# QDRII_mem.net
KiCad netlist of a schematic drawn in Altium Designer
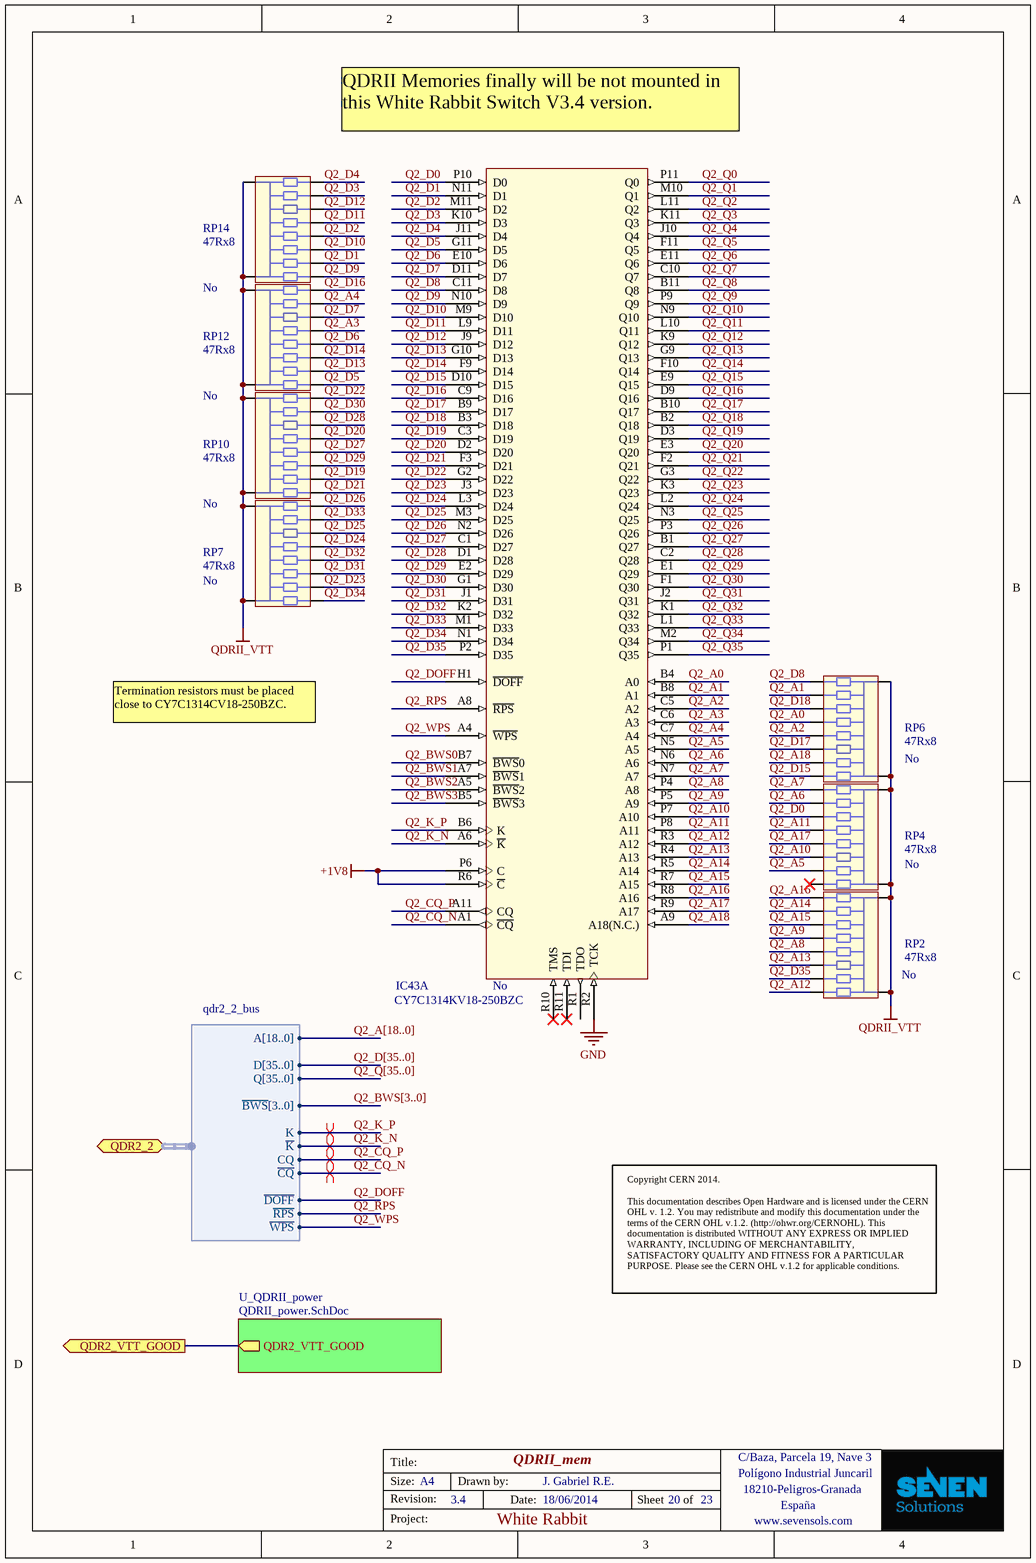
[diagram p0: QDRII_mem.SchDoc]

(export (version "E")
  (design (tool "Eeschema 10.0.6"))
  (components
    (comp (ref "IC43")
      (value "CY7C1314KV18-250BZC")
      (footprint "BGA165C100P11X15_1300X1500X140")
      (description "18-Mbit (512Kx36) QDRII SRAM 2-Word Burst Architecture")
      (fields (field (name "MOUNTED") "No"))
      (libsource (lib "wr_switch") (part "CY7C1314CV18"))
    )
    (comp (ref "RP2")
      (value "47Rx8")
      (footprint "EXBE")
      (description "47R, 62.5mW Chip Resistor Bussed Network")
      (fields
        (field (name "TOLERANCE") "±5%")
        (field (name "MOUNTED") "No")
        (field (name "Comment") "47R x 8")
      )
      (libsource (lib "") (part "EXB-E10C470J_1"))
    )
    (comp (ref "RP4")
      (value "47Rx8")
      (footprint "EXBE")
      (description "47R, 62.5mW Chip Resistor Bussed Network")
      (fields
        (field (name "TOLERANCE") "±5%")
        (field (name "MOUNTED") "No")
        (field (name "Comment") "47R x 8")
      )
      (libsource (lib "") (part "EXB-E10C470J_4"))
    )
    (comp (ref "RP6")
      (value "47Rx8")
      (footprint "EXBE")
      (description "47R, 62.5mW Chip Resistor Bussed Network")
      (fields
        (field (name "TOLERANCE") "±5%")
        (field (name "MOUNTED") "No")
        (field (name "Comment") "47R x 8")
      )
      (libsource (lib "") (part "EXB-E10C470J_3"))
    )
    (comp (ref "RP7")
      (value "47Rx8")
      (footprint "EXBE")
      (description "47R, 62.5mW Chip Resistor Bussed Network")
      (fields
        (field (name "TOLERANCE") "±5%")
        (field (name "MOUNTED") "No")
        (field (name "Comment") "47R x 8")
      )
      (libsource (lib "") (part "EXB-E10C470J_5"))
    )
    (comp (ref "RP10")
      (value "47Rx8")
      (footprint "EXBE")
      (description "47R, 62.5mW Chip Resistor Bussed Network")
      (fields
        (field (name "TOLERANCE") "±5%")
        (field (name "MOUNTED") "No")
        (field (name "Comment") "47R x 8")
      )
      (libsource (lib "") (part "EXB-E10C470J_2"))
    )
    (comp (ref "RP12")
      (value "47Rx8")
      (footprint "EXBE")
      (description "47R, 62.5mW Chip Resistor Bussed Network")
      (fields
        (field (name "TOLERANCE") "±5%")
        (field (name "MOUNTED") "No")
        (field (name "Comment") "47R x 8")
      )
      (libsource (lib "wr_switch") (part "EXB-E10C470J"))
    )
    (comp (ref "RP14")
      (value "47Rx8")
      (footprint "EXBE")
      (description "47R, 62.5mW Chip Resistor Bussed Network")
      (fields
        (field (name "TOLERANCE") "±5%")
        (field (name "MOUNTED") "No")
        (field (name "Comment") "47R x 8")
      )
      (libsource (lib "wr_switch") (part "EXB-E10C470J"))
    )
  )
  (nets
    (net (code "2") (name "+1V8") (class "Default")
      (node (ref "IC43") (pin "P6") (pinfunction "C_P6") (pintype "input"))
      (node (ref "IC43") (pin "R6") (pinfunction "~{C}_R6") (pintype "input"))
    )
    (net (code "3") (name "/Q2_A0") (class "Default")
      (node (ref "IC43") (pin "B4") (pinfunction "A0_B4") (pintype "input"))
      (node (ref "RP6") (pin "8") (pinfunction "8_8") (pintype "passive"))
    )
    (net (code "4") (name "/Q2_A1") (class "Default")
      (node (ref "IC43") (pin "B8") (pinfunction "A1_B8") (pintype "input"))
      (node (ref "RP6") (pin "10") (pinfunction "10_10") (pintype "passive"))
    )
    (net (code "5") (name "/Q2_A2") (class "Default")
      (node (ref "IC43") (pin "C5") (pinfunction "A2_C5") (pintype "input"))
      (node (ref "RP6") (pin "9") (pinfunction "9_9") (pintype "passive"))
    )
    (net (code "6") (name "/Q2_A3") (class "Default")
      (node (ref "IC43") (pin "C6") (pinfunction "A3_C6") (pintype "input"))
      (node (ref "RP12") (pin "7") (pinfunction "7_7") (pintype "passive"))
    )
    (net (code "7") (name "/Q2_A4") (class "Default")
      (node (ref "IC43") (pin "C7") (pinfunction "A4_C7") (pintype "input"))
      (node (ref "RP12") (pin "9") (pinfunction "9_9") (pintype "passive"))
    )
    (net (code "8") (name "/Q2_A5") (class "Default")
      (node (ref "IC43") (pin "N5") (pinfunction "A5_N5") (pintype "input"))
      (node (ref "RP4") (pin "8") (pinfunction "8_8") (pintype "passive"))
    )
    (net (code "9") (name "/Q2_A6") (class "Default")
      (node (ref "IC43") (pin "N6") (pinfunction "A6_N6") (pintype "input"))
      (node (ref "RP4") (pin "9") (pinfunction "9_9") (pintype "passive"))
    )
    (net (code "10") (name "/Q2_A7") (class "Default")
      (node (ref "IC43") (pin "N7") (pinfunction "A7_N7") (pintype "input"))
      (node (ref "RP4") (pin "10") (pinfunction "10_10") (pintype "passive"))
    )
    (net (code "11") (name "/Q2_A8") (class "Default")
      (node (ref "IC43") (pin "P4") (pinfunction "A8_P4") (pintype "input"))
      (node (ref "RP2") (pin "5") (pinfunction "5_5") (pintype "passive"))
    )
    (net (code "12") (name "/Q2_A9") (class "Default")
      (node (ref "IC43") (pin "P5") (pinfunction "A9_P5") (pintype "input"))
      (node (ref "RP2") (pin "8") (pinfunction "8_8") (pintype "passive"))
    )
    (net (code "13") (name "/Q2_A10") (class "Default")
      (node (ref "IC43") (pin "P7") (pinfunction "A10_P7") (pintype "input"))
      (node (ref "RP4") (pin "2") (pinfunction "2_2") (pintype "passive"))
    )
    (net (code "14") (name "/Q2_A11") (class "Default")
      (node (ref "IC43") (pin "P8") (pinfunction "A11_P8") (pintype "input"))
      (node (ref "RP4") (pin "3") (pinfunction "3_3") (pintype "passive"))
    )
    (net (code "15") (name "/Q2_A12") (class "Default")
      (node (ref "IC43") (pin "R3") (pinfunction "A12_R3") (pintype "input"))
      (node (ref "RP2") (pin "2") (pinfunction "2_2") (pintype "passive"))
    )
    (net (code "16") (name "/Q2_A13") (class "Default")
      (node (ref "IC43") (pin "R4") (pinfunction "A13_R4") (pintype "input"))
      (node (ref "RP2") (pin "4") (pinfunction "4_4") (pintype "passive"))
    )
    (net (code "17") (name "/Q2_A14") (class "Default")
      (node (ref "IC43") (pin "R5") (pinfunction "A14_R5") (pintype "input"))
      (node (ref "RP2") (pin "7") (pinfunction "7_7") (pintype "passive"))
    )
    (net (code "18") (name "/Q2_A15") (class "Default")
      (node (ref "IC43") (pin "R7") (pinfunction "A15_R7") (pintype "input"))
      (node (ref "RP2") (pin "9") (pinfunction "9_9") (pintype "passive"))
    )
    (net (code "19") (name "/Q2_A16") (class "Default")
      (node (ref "IC43") (pin "R8") (pinfunction "A16_R8") (pintype "input"))
      (node (ref "RP2") (pin "10") (pinfunction "10_10") (pintype "passive"))
    )
    (net (code "20") (name "/Q2_A17") (class "Default")
      (node (ref "IC43") (pin "R9") (pinfunction "A17_R9") (pintype "input"))
      (node (ref "RP4") (pin "4") (pinfunction "4_4") (pintype "passive"))
    )
    (net (code "21") (name "/Q2_A18") (class "Default")
      (node (ref "IC43") (pin "A9") (pinfunction "A18(N.C.)_A9") (pintype "input"))
      (node (ref "RP6") (pin "3") (pinfunction "3_3") (pintype "passive"))
    )
    (net (code "23") (name "/Q2_BWS0") (class "Default")
      (node (ref "IC43") (pin "B7") (pinfunction "~{BWS}0_B7") (pintype "input"))
    )
    (net (code "24") (name "/Q2_BWS1") (class "Default")
      (node (ref "IC43") (pin "A7") (pinfunction "~{BWS}1_A7") (pintype "input"))
    )
    (net (code "25") (name "/Q2_BWS2") (class "Default")
      (node (ref "IC43") (pin "A5") (pinfunction "~{BWS}2_A5") (pintype "input"))
    )
    (net (code "26") (name "/Q2_BWS3") (class "Default")
      (node (ref "IC43") (pin "B5") (pinfunction "~{BWS}3_B5") (pintype "input"))
    )
    (net (code "27") (name "/Q2_CQ_N") (class "Default")
      (node (ref "IC43") (pin "A1") (pinfunction "~{CQ}_A1") (pintype "output"))
    )
    (net (code "28") (name "/Q2_CQ_P") (class "Default")
      (node (ref "IC43") (pin "A11") (pinfunction "CQ_A11") (pintype "output"))
    )
    (net (code "29") (name "/Q2_D0") (class "Default")
      (node (ref "IC43") (pin "P10") (pinfunction "D0_P10") (pintype "input"))
      (node (ref "RP4") (pin "5") (pinfunction "5_5") (pintype "passive"))
    )
    (net (code "30") (name "/Q2_D1") (class "Default")
      (node (ref "IC43") (pin "N11") (pinfunction "D1_N11") (pintype "input"))
      (node (ref "RP14") (pin "3") (pinfunction "3_3") (pintype "passive"))
    )
    (net (code "31") (name "/Q2_D2") (class "Default")
      (node (ref "IC43") (pin "M11") (pinfunction "D2_M11") (pintype "input"))
      (node (ref "RP14") (pin "5") (pinfunction "5_5") (pintype "passive"))
    )
    (net (code "32") (name "/Q2_D3") (class "Default")
      (node (ref "IC43") (pin "K10") (pinfunction "D3_K10") (pintype "input"))
      (node (ref "RP14") (pin "9") (pinfunction "9_9") (pintype "passive"))
    )
    (net (code "33") (name "/Q2_D4") (class "Default")
      (node (ref "IC43") (pin "J11") (pinfunction "D4_J11") (pintype "input"))
      (node (ref "RP14") (pin "10") (pinfunction "10_10") (pintype "passive"))
    )
    (net (code "34") (name "/Q2_D5") (class "Default")
      (node (ref "IC43") (pin "G11") (pinfunction "D5_G11") (pintype "input"))
      (node (ref "RP12") (pin "2") (pinfunction "2_2") (pintype "passive"))
    )
    (net (code "35") (name "/Q2_D6") (class "Default")
      (node (ref "IC43") (pin "E10") (pinfunction "D6_E10") (pintype "input"))
      (node (ref "RP12") (pin "5") (pinfunction "5_5") (pintype "passive"))
    )
    (net (code "36") (name "/Q2_D7") (class "Default")
      (node (ref "IC43") (pin "D11") (pinfunction "D7_D11") (pintype "input"))
      (node (ref "RP12") (pin "8") (pinfunction "8_8") (pintype "passive"))
    )
    (net (code "37") (name "/Q2_D8") (class "Default")
      (node (ref "IC43") (pin "C11") (pinfunction "D8_C11") (pintype "input"))
      (node (ref "RP6") (pin "5") (pinfunction "5_5") (pintype "passive"))
    )
    (net (code "38") (name "/Q2_D9") (class "Default")
      (node (ref "IC43") (pin "N10") (pinfunction "D9_N10") (pintype "input"))
      (node (ref "RP14") (pin "2") (pinfunction "2_2") (pintype "passive"))
    )
    (net (code "39") (name "/Q2_D10") (class "Default")
      (node (ref "IC43") (pin "M9") (pinfunction "D10_M9") (pintype "input"))
      (node (ref "RP14") (pin "4") (pinfunction "4_4") (pintype "passive"))
    )
    (net (code "40") (name "/Q2_D11") (class "Default")
      (node (ref "IC43") (pin "L9") (pinfunction "D11_L9") (pintype "input"))
      (node (ref "RP14") (pin "7") (pinfunction "7_7") (pintype "passive"))
    )
    (net (code "41") (name "/Q2_D12") (class "Default")
      (node (ref "IC43") (pin "J9") (pinfunction "D12_J9") (pintype "input"))
      (node (ref "RP14") (pin "8") (pinfunction "8_8") (pintype "passive"))
    )
    (net (code "42") (name "/Q2_D13") (class "Default")
      (node (ref "IC43") (pin "G10") (pinfunction "D13_G10") (pintype "input"))
      (node (ref "RP12") (pin "3") (pinfunction "3_3") (pintype "passive"))
    )
    (net (code "43") (name "/Q2_D14") (class "Default")
      (node (ref "IC43") (pin "F9") (pinfunction "D14_F9") (pintype "input"))
      (node (ref "RP12") (pin "4") (pinfunction "4_4") (pintype "passive"))
    )
    (net (code "44") (name "/Q2_D15") (class "Default")
      (node (ref "IC43") (pin "D10") (pinfunction "D15_D10") (pintype "input"))
      (node (ref "RP6") (pin "4") (pinfunction "4_4") (pintype "passive"))
    )
    (net (code "45") (name "/Q2_D16") (class "Default")
      (node (ref "IC43") (pin "C9") (pinfunction "D16_C9") (pintype "input"))
      (node (ref "RP12") (pin "10") (pinfunction "10_10") (pintype "passive"))
    )
    (net (code "46") (name "/Q2_D17") (class "Default")
      (node (ref "IC43") (pin "B9") (pinfunction "D17_B9") (pintype "input"))
      (node (ref "RP6") (pin "2") (pinfunction "2_2") (pintype "passive"))
    )
    (net (code "47") (name "/Q2_D18") (class "Default")
      (node (ref "IC43") (pin "B3") (pinfunction "D18_B3") (pintype "input"))
      (node (ref "RP6") (pin "7") (pinfunction "7_7") (pintype "passive"))
    )
    (net (code "48") (name "/Q2_D19") (class "Default")
      (node (ref "IC43") (pin "C3") (pinfunction "D19_C3") (pintype "input"))
      (node (ref "RP10") (pin "7") (pinfunction "7_7") (pintype "passive"))
    )
    (net (code "49") (name "/Q2_D20") (class "Default")
      (node (ref "IC43") (pin "D2") (pinfunction "D20_D2") (pintype "input"))
      (node (ref "RP10") (pin "9") (pinfunction "9_9") (pintype "passive"))
    )
    (net (code "50") (name "/Q2_D21") (class "Default")
      (node (ref "IC43") (pin "F3") (pinfunction "D21_F3") (pintype "input"))
      (node (ref "RP10") (pin "3") (pinfunction "3_3") (pintype "passive"))
    )
    (net (code "51") (name "/Q2_D22") (class "Default")
      (node (ref "IC43") (pin "G2") (pinfunction "D22_G2") (pintype "input"))
      (node (ref "RP10") (pin "5") (pinfunction "5_5") (pintype "passive"))
    )
    (net (code "52") (name "/Q2_D23") (class "Default")
      (node (ref "IC43") (pin "J3") (pinfunction "D23_J3") (pintype "input"))
      (node (ref "RP7") (pin "7") (pinfunction "7_7") (pintype "passive"))
    )
    (net (code "53") (name "/Q2_D24") (class "Default")
      (node (ref "IC43") (pin "L3") (pinfunction "D24_L3") (pintype "input"))
      (node (ref "RP7") (pin "10") (pinfunction "10_10") (pintype "passive"))
    )
    (net (code "54") (name "/Q2_D25") (class "Default")
      (node (ref "IC43") (pin "M3") (pinfunction "D25_M3") (pintype "input"))
      (node (ref "RP7") (pin "2") (pinfunction "2_2") (pintype "passive"))
    )
    (net (code "55") (name "/Q2_D26") (class "Default")
      (node (ref "IC43") (pin "N2") (pinfunction "D26_N2") (pintype "input"))
      (node (ref "RP7") (pin "4") (pinfunction "4_4") (pintype "passive"))
    )
    (net (code "56") (name "/Q2_D27") (class "Default")
      (node (ref "IC43") (pin "C1") (pinfunction "D27_C1") (pintype "input"))
      (node (ref "RP10") (pin "8") (pinfunction "8_8") (pintype "passive"))
    )
    (net (code "57") (name "/Q2_D28") (class "Default")
      (node (ref "IC43") (pin "D1") (pinfunction "D28_D1") (pintype "input"))
      (node (ref "RP10") (pin "10") (pinfunction "10_10") (pintype "passive"))
    )
    (net (code "58") (name "/Q2_D29") (class "Default")
      (node (ref "IC43") (pin "E2") (pinfunction "D29_E2") (pintype "input"))
      (node (ref "RP10") (pin "2") (pinfunction "2_2") (pintype "passive"))
    )
    (net (code "59") (name "/Q2_D30") (class "Default")
      (node (ref "IC43") (pin "G1") (pinfunction "D30_G1") (pintype "input"))
      (node (ref "RP10") (pin "4") (pinfunction "4_4") (pintype "passive"))
    )
    (net (code "60") (name "/Q2_D31") (class "Default")
      (node (ref "IC43") (pin "J1") (pinfunction "D31_J1") (pintype "input"))
      (node (ref "RP7") (pin "8") (pinfunction "8_8") (pintype "passive"))
    )
    (net (code "61") (name "/Q2_D32") (class "Default")
      (node (ref "IC43") (pin "K2") (pinfunction "D32_K2") (pintype "input"))
      (node (ref "RP7") (pin "9") (pinfunction "9_9") (pintype "passive"))
    )
    (net (code "62") (name "/Q2_D33") (class "Default")
      (node (ref "IC43") (pin "M1") (pinfunction "D33_M1") (pintype "input"))
      (node (ref "RP7") (pin "3") (pinfunction "3_3") (pintype "passive"))
    )
    (net (code "63") (name "/Q2_D34") (class "Default")
      (node (ref "IC43") (pin "N1") (pinfunction "D34_N1") (pintype "input"))
      (node (ref "RP7") (pin "5") (pinfunction "5_5") (pintype "passive"))
    )
    (net (code "64") (name "/Q2_D35") (class "Default")
      (node (ref "IC43") (pin "P2") (pinfunction "D35_P2") (pintype "input"))
      (node (ref "RP2") (pin "3") (pinfunction "3_3") (pintype "passive"))
    )
    (net (code "65") (name "/Q2_DOFF") (class "Default")
      (node (ref "IC43") (pin "H1") (pinfunction "~{DOFF}_H1") (pintype "input"))
    )
    (net (code "67") (name "/Q2_K_N") (class "Default")
      (node (ref "IC43") (pin "A6") (pinfunction "~{K}_A6") (pintype "input"))
    )
    (net (code "68") (name "/Q2_K_P") (class "Default")
      (node (ref "IC43") (pin "B6") (pinfunction "K_B6") (pintype "input"))
    )
    (net (code "69") (name "/Q2_Q0") (class "Default")
      (node (ref "IC43") (pin "P11") (pinfunction "Q0_P11") (pintype "output"))
    )
    (net (code "70") (name "/Q2_Q1") (class "Default")
      (node (ref "IC43") (pin "M10") (pinfunction "Q1_M10") (pintype "output"))
    )
    (net (code "71") (name "/Q2_Q2") (class "Default")
      (node (ref "IC43") (pin "L11") (pinfunction "Q2_L11") (pintype "output"))
    )
    (net (code "72") (name "/Q2_Q3") (class "Default")
      (node (ref "IC43") (pin "K11") (pinfunction "Q3_K11") (pintype "output"))
    )
    (net (code "73") (name "/Q2_Q4") (class "Default")
      (node (ref "IC43") (pin "J10") (pinfunction "Q4_J10") (pintype "output"))
    )
    (net (code "74") (name "/Q2_Q5") (class "Default")
      (node (ref "IC43") (pin "F11") (pinfunction "Q5_F11") (pintype "output"))
    )
    (net (code "75") (name "/Q2_Q6") (class "Default")
      (node (ref "IC43") (pin "E11") (pinfunction "Q6_E11") (pintype "output"))
    )
    (net (code "76") (name "/Q2_Q7") (class "Default")
      (node (ref "IC43") (pin "C10") (pinfunction "Q7_C10") (pintype "output"))
    )
    (net (code "77") (name "/Q2_Q8") (class "Default")
      (node (ref "IC43") (pin "B11") (pinfunction "Q8_B11") (pintype "output"))
    )
    (net (code "78") (name "/Q2_Q9") (class "Default")
      (node (ref "IC43") (pin "P9") (pinfunction "Q9_P9") (pintype "output"))
    )
    (net (code "79") (name "/Q2_Q10") (class "Default")
      (node (ref "IC43") (pin "N9") (pinfunction "Q10_N9") (pintype "output"))
    )
    (net (code "80") (name "/Q2_Q11") (class "Default")
      (node (ref "IC43") (pin "L10") (pinfunction "Q11_L10") (pintype "output"))
    )
    (net (code "81") (name "/Q2_Q12") (class "Default")
      (node (ref "IC43") (pin "K9") (pinfunction "Q12_K9") (pintype "output"))
    )
    (net (code "82") (name "/Q2_Q13") (class "Default")
      (node (ref "IC43") (pin "G9") (pinfunction "Q13_G9") (pintype "output"))
    )
    (net (code "83") (name "/Q2_Q14") (class "Default")
      (node (ref "IC43") (pin "F10") (pinfunction "Q14_F10") (pintype "output"))
    )
    (net (code "84") (name "/Q2_Q15") (class "Default")
      (node (ref "IC43") (pin "E9") (pinfunction "Q15_E9") (pintype "output"))
    )
    (net (code "85") (name "/Q2_Q16") (class "Default")
      (node (ref "IC43") (pin "D9") (pinfunction "Q16_D9") (pintype "output"))
    )
    (net (code "86") (name "/Q2_Q17") (class "Default")
      (node (ref "IC43") (pin "B10") (pinfunction "Q17_B10") (pintype "output"))
    )
    (net (code "87") (name "/Q2_Q18") (class "Default")
      (node (ref "IC43") (pin "B2") (pinfunction "Q18_B2") (pintype "output"))
    )
    (net (code "88") (name "/Q2_Q19") (class "Default")
      (node (ref "IC43") (pin "D3") (pinfunction "Q19_D3") (pintype "output"))
    )
    (net (code "89") (name "/Q2_Q20") (class "Default")
      (node (ref "IC43") (pin "E3") (pinfunction "Q20_E3") (pintype "output"))
    )
    (net (code "90") (name "/Q2_Q21") (class "Default")
      (node (ref "IC43") (pin "F2") (pinfunction "Q21_F2") (pintype "output"))
    )
    (net (code "91") (name "/Q2_Q22") (class "Default")
      (node (ref "IC43") (pin "G3") (pinfunction "Q22_G3") (pintype "output"))
    )
    (net (code "92") (name "/Q2_Q23") (class "Default")
      (node (ref "IC43") (pin "K3") (pinfunction "Q23_K3") (pintype "output"))
    )
    (net (code "93") (name "/Q2_Q24") (class "Default")
      (node (ref "IC43") (pin "L2") (pinfunction "Q24_L2") (pintype "output"))
    )
    (net (code "94") (name "/Q2_Q25") (class "Default")
      (node (ref "IC43") (pin "N3") (pinfunction "Q25_N3") (pintype "output"))
    )
    (net (code "95") (name "/Q2_Q26") (class "Default")
      (node (ref "IC43") (pin "P3") (pinfunction "Q26_P3") (pintype "output"))
    )
    (net (code "96") (name "/Q2_Q27") (class "Default")
      (node (ref "IC43") (pin "B1") (pinfunction "Q27_B1") (pintype "output"))
    )
    (net (code "97") (name "/Q2_Q28") (class "Default")
      (node (ref "IC43") (pin "C2") (pinfunction "Q28_C2") (pintype "output"))
    )
    (net (code "98") (name "/Q2_Q29") (class "Default")
      (node (ref "IC43") (pin "E1") (pinfunction "Q29_E1") (pintype "output"))
    )
    (net (code "99") (name "/Q2_Q30") (class "Default")
      (node (ref "IC43") (pin "F1") (pinfunction "Q30_F1") (pintype "output"))
    )
    (net (code "100") (name "/Q2_Q31") (class "Default")
      (node (ref "IC43") (pin "J2") (pinfunction "Q31_J2") (pintype "output"))
    )
    (net (code "101") (name "/Q2_Q32") (class "Default")
      (node (ref "IC43") (pin "K1") (pinfunction "Q32_K1") (pintype "output"))
    )
    (net (code "102") (name "/Q2_Q33") (class "Default")
      (node (ref "IC43") (pin "L1") (pinfunction "Q33_L1") (pintype "output"))
    )
    (net (code "103") (name "/Q2_Q34") (class "Default")
      (node (ref "IC43") (pin "M2") (pinfunction "Q34_M2") (pintype "output"))
    )
    (net (code "104") (name "/Q2_Q35") (class "Default")
      (node (ref "IC43") (pin "P1") (pinfunction "Q35_P1") (pintype "output"))
    )
    (net (code "106") (name "/Q2_RPS") (class "Default")
      (node (ref "IC43") (pin "A8") (pinfunction "~{RPS}_A8") (pintype "input"))
    )
    (net (code "107") (name "/Q2_WPS") (class "Default")
      (node (ref "IC43") (pin "A4") (pinfunction "~{WPS}_A4") (pintype "input"))
    )
    (net (code "111") (name "GND") (class "Default")
      (node (ref "IC43") (pin "R2") (pinfunction "TCK_R2") (pintype "input"))
    )
    (net (code "112") (name "QDRII_VTT") (class "Default")
      (node (ref "RP10") (pin "1") (pinfunction "1_1") (pintype "passive"))
      (node (ref "RP10") (pin "6") (pinfunction "6_6") (pintype "passive"))
      (node (ref "RP12") (pin "1") (pinfunction "1_1") (pintype "passive"))
      (node (ref "RP12") (pin "6") (pinfunction "6_6") (pintype "passive"))
      (node (ref "RP14") (pin "1") (pinfunction "1_1") (pintype "passive"))
      (node (ref "RP14") (pin "6") (pinfunction "6_6") (pintype "passive"))
      (node (ref "RP2") (pin "1") (pinfunction "1_1") (pintype "passive"))
      (node (ref "RP2") (pin "6") (pinfunction "6_6") (pintype "passive"))
      (node (ref "RP4") (pin "1") (pinfunction "1_1") (pintype "passive"))
      (node (ref "RP4") (pin "6") (pinfunction "6_6") (pintype "passive"))
      (node (ref "RP6") (pin "1") (pinfunction "1_1") (pintype "passive"))
      (node (ref "RP6") (pin "6") (pinfunction "6_6") (pintype "passive"))
      (node (ref "RP7") (pin "1") (pinfunction "1_1") (pintype "passive"))
      (node (ref "RP7") (pin "6") (pinfunction "6_6") (pintype "passive"))
    )
    (net (code "113") (name "unconnected-(IC43A-TDI-PadR11)") (class "Default")
      (node (ref "IC43") (pin "R11") (pinfunction "TDI_R11") (pintype "input+no_connect"))
    )
    (net (code "114") (name "unconnected-(IC43A-TDO-PadR1)") (class "Default")
      (node (ref "IC43") (pin "R1") (pinfunction "TDO_R1") (pintype "output"))
    )
    (net (code "115") (name "unconnected-(IC43A-TMS-PadR10)") (class "Default")
      (node (ref "IC43") (pin "R10") (pinfunction "TMS_R10") (pintype "input+no_connect"))
    )
    (net (code "116") (name "unconnected-(RP4-Pad7)") (class "Default")
      (node (ref "RP4") (pin "7") (pinfunction "7_7") (pintype "passive+no_connect"))
    )
  )
)
